# GateDriver.net
KiCad netlist of a schematic drawn in Altium Designer
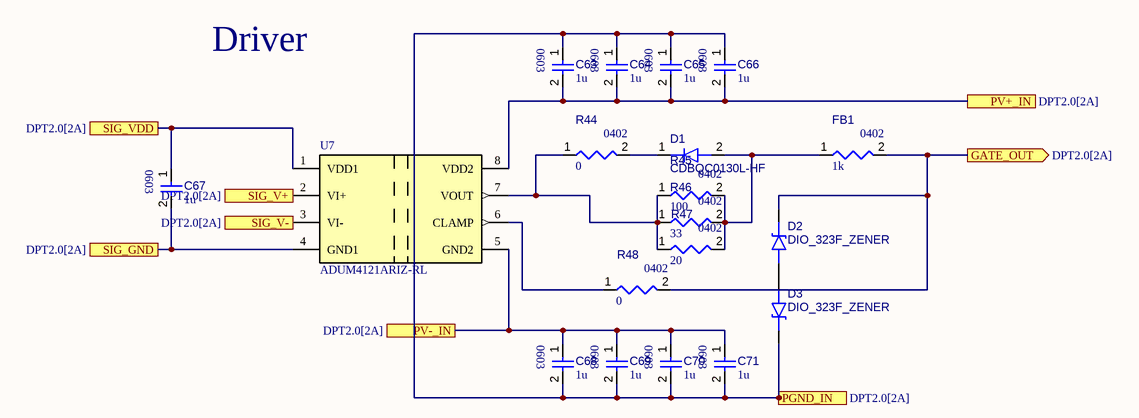
[diagram p0: GateDriver.SchDoc]

(export (version "E")
  (design (tool "Eeschema 10.0.6"))
  (components
    (comp (ref "C63")
      (value "1u")
      (footprint "CAP_0603_HIGH")
      (description "Non polarized SMD capacitor - 0603 (1608 Metric)")
      (fields (field (name "Comment") "CAP-0603"))
      (libsource (lib "2256-GaN Power") (part "CAP-NP-2"))
    )
    (comp (ref "C64")
      (value "1u")
      (footprint "CAP_0603_HIGH")
      (description "Non polarized SMD capacitor - 0603 (1608 Metric)")
      (fields (field (name "Comment") "CAP-0603"))
      (libsource (lib "2256-GaN Power") (part "CAP-NP-2"))
    )
    (comp (ref "C65")
      (value "1u")
      (footprint "CAP_0603_HIGH")
      (description "Non polarized SMD capacitor - 0603 (1608 Metric)")
      (fields (field (name "Comment") "CAP-0603"))
      (libsource (lib "2256-GaN Power") (part "CAP-NP-2"))
    )
    (comp (ref "C66")
      (value "1u")
      (footprint "CAP_0603_HIGH")
      (description "Non polarized SMD capacitor - 0603 (1608 Metric)")
      (fields (field (name "Comment") "CAP-0603"))
      (libsource (lib "2256-GaN Power") (part "CAP-NP-2"))
    )
    (comp (ref "C67")
      (value "1u")
      (footprint "CAP_0603_HIGH")
      (description "Non polarized SMD capacitor - 0603 (1608 Metric)")
      (fields (field (name "Comment") "CAP-0603"))
      (libsource (lib "2256-GaN Power") (part "CAP-NP-2"))
    )
    (comp (ref "C68")
      (value "1u")
      (footprint "CAP_0603_HIGH")
      (description "Non polarized SMD capacitor - 0603 (1608 Metric)")
      (fields (field (name "Comment") "CAP-0603"))
      (libsource (lib "2256-GaN Power") (part "CAP-NP-2"))
    )
    (comp (ref "C69")
      (value "1u")
      (footprint "CAP_0603_HIGH")
      (description "Non polarized SMD capacitor - 0603 (1608 Metric)")
      (fields (field (name "Comment") "CAP-0603"))
      (libsource (lib "2256-GaN Power") (part "CAP-NP-2"))
    )
    (comp (ref "C70")
      (value "1u")
      (footprint "CAP_0603_HIGH")
      (description "Non polarized SMD capacitor - 0603 (1608 Metric)")
      (fields (field (name "Comment") "CAP-0603"))
      (libsource (lib "2256-GaN Power") (part "CAP-NP-2"))
    )
    (comp (ref "C71")
      (value "1u")
      (footprint "CAP_0603_HIGH")
      (description "Non polarized SMD capacitor - 0603 (1608 Metric)")
      (fields (field (name "Comment") "CAP-0603"))
      (libsource (lib "2256-GaN Power") (part "CAP-NP-2"))
    )
    (comp (ref "D1")
      (value "CDBQC0130L-HF")
      (footprint "DIO_SOD-923F")
      (description "Low VF SMD Schottky Barrier Diode")
      (libsource (lib "2256-GaN Power") (part "DIODE-2"))
    )
    (comp (ref "D2")
      (value "DIO_323F_ZENER")
      (footprint "DIO_SOD-323F")
      (description "Generic SOD-323F Zener diode")
      (libsource (lib "2256-GaN Power") (part "DIODE-ZEN-2"))
    )
    (comp (ref "D3")
      (value "DIO_323F_ZENER")
      (footprint "DIO_SOD-323F")
      (description "Generic SOD-323F Zener diode")
      (libsource (lib "2256-GaN Power") (part "DIODE-ZEN-2"))
    )
    (comp (ref "FB1")
      (value "1k")
      (footprint "RES_0402_HIGH")
      (description "SMD Resistor - 0402 (1005 Metric)")
      (fields (field (name "Comment") "RES-0402"))
      (libsource (lib "2256-GaN Power") (part "RES-2"))
    )
    (comp (ref "R44")
      (value "0")
      (footprint "RES_0402_HIGH")
      (description "SMD Resistor - 0402 (1005 Metric)")
      (fields (field (name "Comment") "RES-0402"))
      (libsource (lib "2256-GaN Power") (part "RES-2"))
    )
    (comp (ref "R45")
      (value "100")
      (footprint "RES_0402_HIGH")
      (description "SMD Resistor - 0402 (1005 Metric)")
      (fields (field (name "Comment") "RES-0402"))
      (libsource (lib "2256-GaN Power") (part "RES-2"))
    )
    (comp (ref "R46")
      (value "33")
      (footprint "RES_0402_HIGH")
      (description "SMD Resistor - 0402 (1005 Metric)")
      (fields (field (name "Comment") "RES-0402"))
      (libsource (lib "2256-GaN Power") (part "RES-2"))
    )
    (comp (ref "R47")
      (value "20")
      (footprint "RES_0402_HIGH")
      (description "SMD Resistor - 0402 (1005 Metric)")
      (fields (field (name "Comment") "RES-0402"))
      (libsource (lib "2256-GaN Power") (part "RES-2"))
    )
    (comp (ref "R48")
      (value "0")
      (footprint "RES_0402_HIGH")
      (description "SMD Resistor - 0402 (1005 Metric)")
      (fields (field (name "Comment") "RES-0402"))
      (libsource (lib "2256-GaN Power") (part "RES-2"))
    )
    (comp (ref "U7")
      (value "ADUM4121ARIZ-RL")
      (footprint "SOIC-8_WIDE")
      (description "DGTL ISO 5KV 1CH GATE DRVR 8SOIC")
      (libsource (lib "2256-GaN Power") (part "ADUM4121"))
    )
  )
  (nets
    (net (code "1") (name "/GATE_OUT") (class "Default")
      (node (ref "D2") (pin "1") (pinfunction "K_1") (pintype "passive"))
      (node (ref "FB1") (pin "2") (pinfunction "2_2") (pintype "passive"))
      (node (ref "R48") (pin "2") (pinfunction "2_2") (pintype "passive"))
    )
    (net (code "2") (name "/PGND_IN") (class "Default")
      (node (ref "C63") (pin "1") (pinfunction "1_1") (pintype "passive"))
      (node (ref "C64") (pin "1") (pinfunction "1_1") (pintype "passive"))
      (node (ref "C65") (pin "1") (pinfunction "1_1") (pintype "passive"))
      (node (ref "C66") (pin "1") (pinfunction "1_1") (pintype "passive"))
      (node (ref "C68") (pin "2") (pinfunction "2_2") (pintype "passive"))
      (node (ref "C69") (pin "2") (pinfunction "2_2") (pintype "passive"))
      (node (ref "C70") (pin "2") (pinfunction "2_2") (pintype "passive"))
      (node (ref "C71") (pin "2") (pinfunction "2_2") (pintype "passive"))
      (node (ref "D3") (pin "1") (pinfunction "K_1") (pintype "passive"))
    )
    (net (code "3") (name "/PV+_IN") (class "Default")
      (node (ref "C63") (pin "2") (pinfunction "2_2") (pintype "passive"))
      (node (ref "C64") (pin "2") (pinfunction "2_2") (pintype "passive"))
      (node (ref "C65") (pin "2") (pinfunction "2_2") (pintype "passive"))
      (node (ref "C66") (pin "2") (pinfunction "2_2") (pintype "passive"))
      (node (ref "U7") (pin "8") (pinfunction "VDD2_8") (pintype "power_in"))
    )
    (net (code "4") (name "/PV-_IN") (class "Default")
      (node (ref "C68") (pin "1") (pinfunction "1_1") (pintype "passive"))
      (node (ref "C69") (pin "1") (pinfunction "1_1") (pintype "passive"))
      (node (ref "C70") (pin "1") (pinfunction "1_1") (pintype "passive"))
      (node (ref "C71") (pin "1") (pinfunction "1_1") (pintype "passive"))
      (node (ref "U7") (pin "5") (pinfunction "GND2_5") (pintype "power_in"))
    )
    (net (code "5") (name "/SIG_GND") (class "Default")
      (node (ref "C67") (pin "2") (pinfunction "2_2") (pintype "passive"))
      (node (ref "U7") (pin "4") (pinfunction "GND1_4") (pintype "power_in"))
    )
    (net (code "6") (name "/SIG_V+") (class "Default")
      (node (ref "U7") (pin "2") (pinfunction "VI+_2") (pintype "passive"))
    )
    (net (code "7") (name "/SIG_V-") (class "Default")
      (node (ref "U7") (pin "3") (pinfunction "VI-_3") (pintype "passive"))
    )
    (net (code "8") (name "/SIG_VDD") (class "Default")
      (node (ref "C67") (pin "1") (pinfunction "1_1") (pintype "passive"))
      (node (ref "U7") (pin "1") (pinfunction "VDD1_1") (pintype "power_in"))
    )
    (net (code "9") (name "Net-(D1-A)") (class "Default")
      (node (ref "D1") (pin "2") (pinfunction "A_2") (pintype "passive"))
      (node (ref "FB1") (pin "1") (pinfunction "1_1") (pintype "passive"))
      (node (ref "R45") (pin "2") (pinfunction "2_2") (pintype "passive"))
      (node (ref "R46") (pin "2") (pinfunction "2_2") (pintype "passive"))
      (node (ref "R47") (pin "2") (pinfunction "2_2") (pintype "passive"))
    )
    (net (code "10") (name "Net-(D1-K)") (class "Default")
      (node (ref "D1") (pin "1") (pinfunction "K_1") (pintype "passive"))
      (node (ref "R44") (pin "2") (pinfunction "2_2") (pintype "passive"))
    )
    (net (code "11") (name "Net-(D2-A)") (class "Default")
      (node (ref "D2") (pin "2") (pinfunction "A_2") (pintype "passive"))
      (node (ref "D3") (pin "2") (pinfunction "A_2") (pintype "passive"))
    )
    (net (code "12") (name "Net-(U7-CLAMP)") (class "Default")
      (node (ref "R48") (pin "1") (pinfunction "1_1") (pintype "passive"))
      (node (ref "U7") (pin "6") (pinfunction "CLAMP_6") (pintype "output"))
    )
    (net (code "13") (name "Net-(U7-VOUT)") (class "Default")
      (node (ref "R44") (pin "1") (pinfunction "1_1") (pintype "passive"))
      (node (ref "R45") (pin "1") (pinfunction "1_1") (pintype "passive"))
      (node (ref "R46") (pin "1") (pinfunction "1_1") (pintype "passive"))
      (node (ref "R47") (pin "1") (pinfunction "1_1") (pintype "passive"))
      (node (ref "U7") (pin "7") (pinfunction "VOUT_7") (pintype "output"))
    )
  )
)
